# AC6901Demo1.net
KiCad netlist of a schematic drawn in Altium Designer
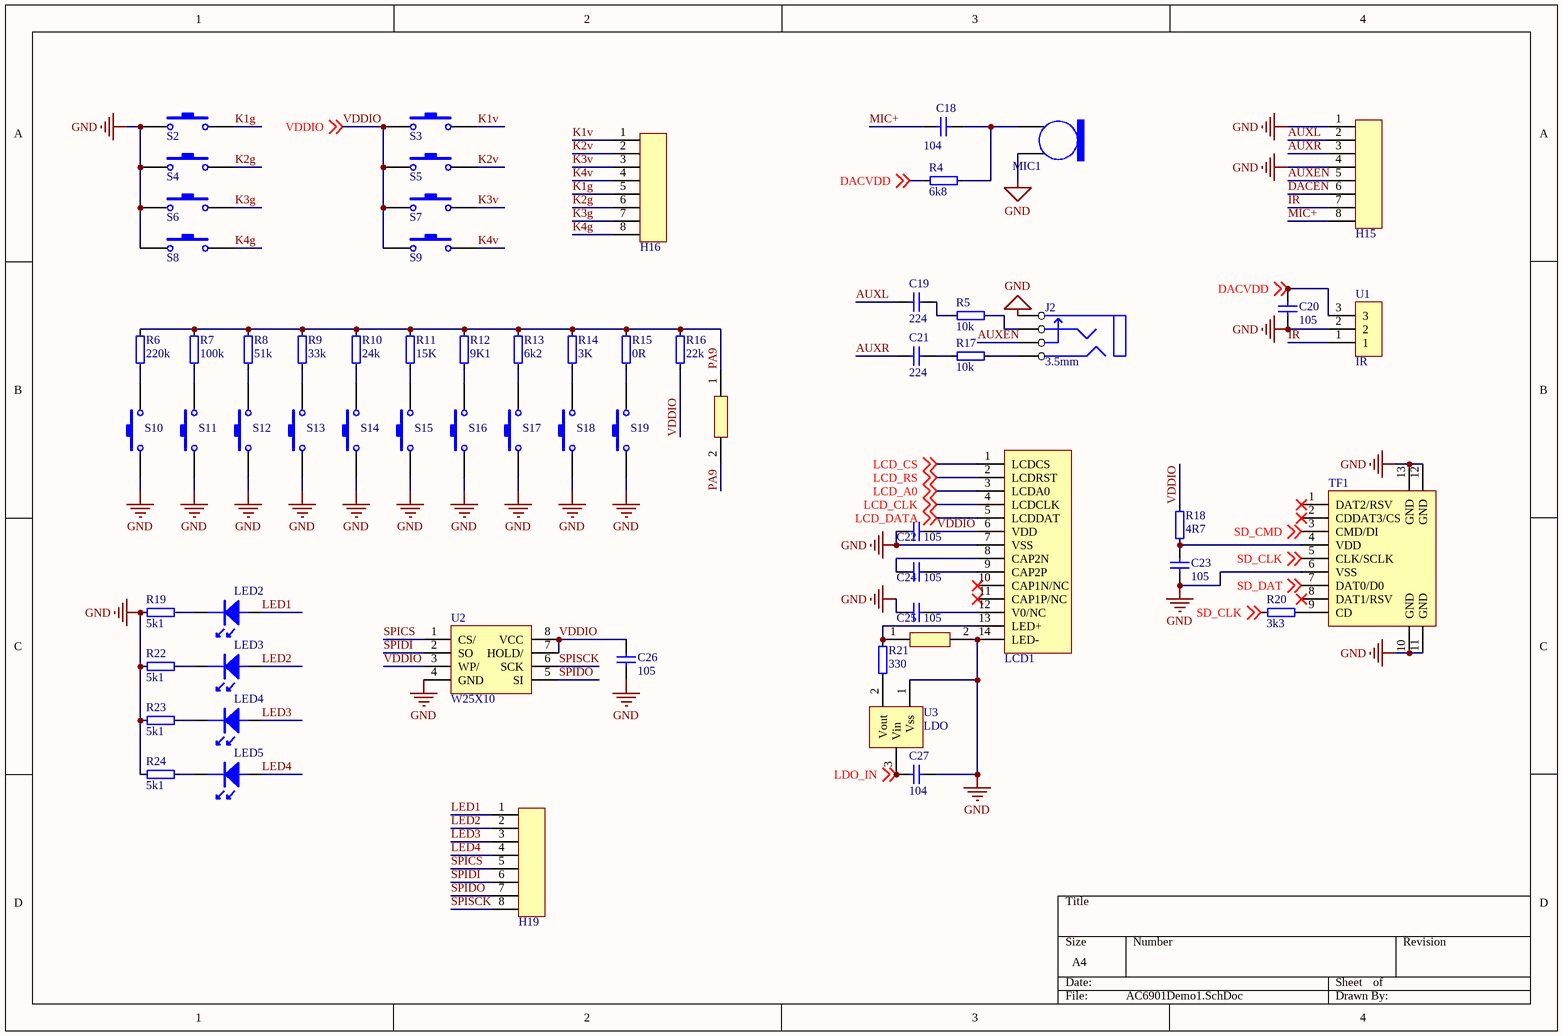
[diagram p0: AC6901Demo1.SchDoc]

(export (version "E")
  (design (tool "Eeschema 10.0.6"))
  (components
    (comp (ref "C18") (value "104") (footprint "Demo:C 0805") (libsource (lib "Demo") (part "CAP-MLCC")))
    (comp (ref "C19") (value "224") (footprint "Demo:C 0805") (libsource (lib "Demo") (part "CAP-MLCC")))
    (comp (ref "C20") (value "105") (footprint "Demo:C 0805") (libsource (lib "Demo") (part "CAP-MLCC")))
    (comp (ref "C21") (value "224") (footprint "Demo:C 0805") (libsource (lib "Demo") (part "CAP-MLCC")))
    (comp (ref "C22") (value "105") (footprint "Demo:C 0805") (libsource (lib "Demo") (part "CAP-MLCC")))
    (comp (ref "C23") (value "105") (footprint "Demo:C 0805") (libsource (lib "Demo") (part "CAP-MLCC")))
    (comp (ref "C24") (value "105") (footprint "Demo:C 0805") (libsource (lib "Demo") (part "CAP-MLCC")))
    (comp (ref "C25") (value "105") (footprint "Demo:C 0805") (libsource (lib "Demo") (part "CAP-MLCC")))
    (comp (ref "C26") (value "105") (footprint "Demo:C 0805") (libsource (lib "Demo") (part "CAP-MLCC")))
    (comp (ref "C27") (value "104") (footprint "Demo:C 0805") (libsource (lib "Demo") (part "CAP-MLCC")))
    (comp (ref "H15") (value "HDR1X8") (footprint "Demo:HDR1X8") (libsource (lib "Demo") (part "HDR1X8")))
    (comp (ref "H16") (value "HDR1X8") (footprint "Demo:HDR1X8") (libsource (lib "Demo") (part "HDR1X8")))
    (comp (ref "H17") (value "HDR2X1") (footprint "Demo:HDR2X1") (libsource (lib "") (part "HDR2X1_1")))
    (comp (ref "H18") (value "HDR2X1") (footprint "Demo:HDR2X1") (libsource (lib "Demo") (part "HDR2X1")))
    (comp (ref "H19") (value "HDR1X8") (footprint "Demo:HDR1X8") (libsource (lib "Demo") (part "HDR1X8")))
    (comp (ref "J2") (value "3.5mm") (footprint "Demo:AUX-3.5") (libsource (lib "Demo") (part "立体声插头")))
    (comp (ref "LCD1")
      (value "LCD12864_ST7567")
      (footprint "Demo:FPC-SMD_P0.80-14P")
      (libsource (lib "Demo") (part "LCD12864_ST7567"))
    )
    (comp (ref "LED2") (value "LED") (footprint "Demo:LED 0805B") (libsource (lib "Demo") (part "LED")))
    (comp (ref "LED3") (value "LED") (footprint "Demo:LED 0805B") (libsource (lib "Demo") (part "LED")))
    (comp (ref "LED4") (value "LED") (footprint "Demo:LED 0805B") (libsource (lib "Demo") (part "LED")))
    (comp (ref "LED5") (value "LED") (footprint "Demo:LED 0805B") (libsource (lib "Demo") (part "LED")))
    (comp (ref "MIC1") (value "MIC") (footprint "Demo:MIC") (libsource (lib "Demo") (part "MIC")))
    (comp (ref "R4") (value "6k8") (footprint "Demo:R 0805") (libsource (lib "Demo") (part "RES")))
    (comp (ref "R5") (value "10k") (footprint "Demo:R 0805") (libsource (lib "Demo") (part "RES")))
    (comp (ref "R6") (value "220k") (footprint "Demo:R 0805") (libsource (lib "Demo") (part "RES")))
    (comp (ref "R7") (value "100k") (footprint "Demo:R 0805") (libsource (lib "Demo") (part "RES")))
    (comp (ref "R8") (value "51k") (footprint "Demo:R 0805") (libsource (lib "Demo") (part "RES")))
    (comp (ref "R9") (value "33k") (footprint "Demo:R 0805") (libsource (lib "Demo") (part "RES")))
    (comp (ref "R10") (value "24k") (footprint "Demo:R 0805") (libsource (lib "Demo") (part "RES")))
    (comp (ref "R11") (value "15K") (footprint "Demo:R 0805") (libsource (lib "Demo") (part "RES")))
    (comp (ref "R12") (value "9K1") (footprint "Demo:R 0805") (libsource (lib "Demo") (part "RES")))
    (comp (ref "R13") (value "6k2") (footprint "Demo:R 0805") (libsource (lib "Demo") (part "RES")))
    (comp (ref "R14") (value "3K") (footprint "Demo:R 0805") (libsource (lib "Demo") (part "RES")))
    (comp (ref "R15") (value "0R") (footprint "Demo:R 0805") (libsource (lib "Demo") (part "RES")))
    (comp (ref "R16") (value "22k") (footprint "Demo:R 0805") (libsource (lib "Demo") (part "RES")))
    (comp (ref "R17") (value "10k") (footprint "Demo:R 0805") (libsource (lib "Demo") (part "RES")))
    (comp (ref "R18") (value "4R7") (footprint "Demo:R 0805") (libsource (lib "Demo") (part "RES")))
    (comp (ref "R19") (value "5k1") (footprint "Demo:R 0805") (libsource (lib "Demo") (part "RES")))
    (comp (ref "R20") (value "3k3") (footprint "Demo:R 0805") (libsource (lib "Demo") (part "RES")))
    (comp (ref "R21") (value "330") (footprint "Demo:R 0805") (libsource (lib "Demo") (part "RES")))
    (comp (ref "R22") (value "5k1") (footprint "Demo:R 0805") (libsource (lib "Demo") (part "RES")))
    (comp (ref "R23") (value "5k1") (footprint "Demo:R 0805") (libsource (lib "Demo") (part "RES")))
    (comp (ref "R24") (value "5k1") (footprint "Demo:R 0805") (libsource (lib "Demo") (part "RES")))
    (comp (ref "S2")
      (value "SW-PB")
      (footprint "Demo:TSW SMD-3*6*2.5")
      (fields (field (name "PUBLISHER") "Altium Limited"))
      (libsource (lib "Demo") (part "SW-PB"))
    )
    (comp (ref "S3")
      (value "SW-PB")
      (footprint "Demo:TSW SMD-3*6*2.5")
      (fields (field (name "PUBLISHER") "Altium Limited"))
      (libsource (lib "Demo") (part "SW-PB"))
    )
    (comp (ref "S4")
      (value "SW-PB")
      (footprint "Demo:TSW SMD-3*6*2.5")
      (fields (field (name "PUBLISHER") "Altium Limited"))
      (libsource (lib "Demo") (part "SW-PB"))
    )
    (comp (ref "S5")
      (value "SW-PB")
      (footprint "Demo:TSW SMD-3*6*2.5")
      (fields (field (name "PUBLISHER") "Altium Limited"))
      (libsource (lib "Demo") (part "SW-PB"))
    )
    (comp (ref "S6")
      (value "SW-PB")
      (footprint "Demo:TSW SMD-3*6*2.5")
      (fields (field (name "PUBLISHER") "Altium Limited"))
      (libsource (lib "Demo") (part "SW-PB"))
    )
    (comp (ref "S7")
      (value "SW-PB")
      (footprint "Demo:TSW SMD-3*6*2.5")
      (fields (field (name "PUBLISHER") "Altium Limited"))
      (libsource (lib "Demo") (part "SW-PB"))
    )
    (comp (ref "S8")
      (value "SW-PB")
      (footprint "Demo:TSW SMD-3*6*2.5")
      (fields (field (name "PUBLISHER") "Altium Limited"))
      (libsource (lib "Demo") (part "SW-PB"))
    )
    (comp (ref "S9")
      (value "SW-PB")
      (footprint "Demo:TSW SMD-3*6*2.5")
      (fields (field (name "PUBLISHER") "Altium Limited"))
      (libsource (lib "Demo") (part "SW-PB"))
    )
    (comp (ref "S10")
      (value "SW-PB")
      (footprint "Demo:TSW SMD-3*6*2.5")
      (fields (field (name "PUBLISHER") "Altium Limited"))
      (libsource (lib "Demo") (part "SW-PB"))
    )
    (comp (ref "S11")
      (value "SW-PB")
      (footprint "Demo:TSW SMD-3*6*2.5")
      (fields (field (name "PUBLISHER") "Altium Limited"))
      (libsource (lib "Demo") (part "SW-PB"))
    )
    (comp (ref "S12")
      (value "SW-PB")
      (footprint "Demo:TSW SMD-3*6*2.5")
      (fields (field (name "PUBLISHER") "Altium Limited"))
      (libsource (lib "Demo") (part "SW-PB"))
    )
    (comp (ref "S13")
      (value "SW-PB")
      (footprint "Demo:TSW SMD-3*6*2.5")
      (fields (field (name "PUBLISHER") "Altium Limited"))
      (libsource (lib "Demo") (part "SW-PB"))
    )
    (comp (ref "S14")
      (value "SW-PB")
      (footprint "Demo:TSW SMD-3*6*2.5")
      (fields (field (name "PUBLISHER") "Altium Limited"))
      (libsource (lib "Demo") (part "SW-PB"))
    )
    (comp (ref "S15")
      (value "SW-PB")
      (footprint "Demo:TSW SMD-3*6*2.5")
      (fields (field (name "PUBLISHER") "Altium Limited"))
      (libsource (lib "Demo") (part "SW-PB"))
    )
    (comp (ref "S16")
      (value "SW-PB")
      (footprint "Demo:TSW SMD-3*6*2.5")
      (fields (field (name "PUBLISHER") "Altium Limited"))
      (libsource (lib "Demo") (part "SW-PB"))
    )
    (comp (ref "S17")
      (value "SW-PB")
      (footprint "Demo:TSW SMD-3*6*2.5")
      (fields (field (name "PUBLISHER") "Altium Limited"))
      (libsource (lib "Demo") (part "SW-PB"))
    )
    (comp (ref "S18")
      (value "SW-PB")
      (footprint "Demo:TSW SMD-3*6*2.5")
      (fields (field (name "PUBLISHER") "Altium Limited"))
      (libsource (lib "Demo") (part "SW-PB"))
    )
    (comp (ref "S19")
      (value "SW-PB")
      (footprint "Demo:TSW SMD-3*6*2.5")
      (fields (field (name "PUBLISHER") "Altium Limited"))
      (libsource (lib "Demo") (part "SW-PB"))
    )
    (comp (ref "TF1") (value "TF") (footprint "Demo:TF") (libsource (lib "Demo") (part "TF")))
    (comp (ref "U1") (value "IR") (footprint "Demo:IR") (libsource (lib "Demo") (part "IR")))
    (comp (ref "U2") (value "W25X10") (footprint "Demo:SOIC8") (libsource (lib "Demo") (part "W25X10")))
    (comp (ref "U3") (value "LDO") (footprint "Demo:SOT23-3L") (libsource (lib "Demo") (part "LDO")))
  )
  (nets
    (net (code "1") (name "/AUXEN") (class "Default")
      (node (ref "H15") (pin "5") (pinfunction "5_5") (pintype "passive"))
      (node (ref "J2") (pin "4") (pinfunction "4_4") (pintype "passive"))
    )
    (net (code "2") (name "/AUXL") (class "Default")
      (node (ref "C19") (pin "1") (pinfunction "1_1") (pintype "passive"))
      (node (ref "H15") (pin "2") (pinfunction "2_2") (pintype "passive"))
    )
    (net (code "3") (name "/AUXR") (class "Default")
      (node (ref "C21") (pin "1") (pinfunction "1_1") (pintype "passive"))
      (node (ref "H15") (pin "3") (pinfunction "3_3") (pintype "passive"))
    )
    (net (code "4") (name "/DACEN") (class "Default")
      (node (ref "H15") (pin "6") (pinfunction "6_6") (pintype "passive"))
    )
    (net (code "5") (name "/IR") (class "Default")
      (node (ref "H15") (pin "7") (pinfunction "7_7") (pintype "passive"))
      (node (ref "U1") (pin "1") (pinfunction "1_1") (pintype "passive"))
    )
    (net (code "6") (name "/K1g") (class "Default")
      (node (ref "H16") (pin "5") (pinfunction "5_5") (pintype "passive"))
      (node (ref "S2") (pin "2") (pinfunction "2_2") (pintype "passive"))
    )
    (net (code "7") (name "/K1v") (class "Default")
      (node (ref "H16") (pin "1") (pinfunction "1_1") (pintype "passive"))
      (node (ref "S3") (pin "2") (pinfunction "2_2") (pintype "passive"))
    )
    (net (code "8") (name "/K2g") (class "Default")
      (node (ref "H16") (pin "6") (pinfunction "6_6") (pintype "passive"))
      (node (ref "S4") (pin "2") (pinfunction "2_2") (pintype "passive"))
    )
    (net (code "9") (name "/K2v") (class "Default")
      (node (ref "H16") (pin "2") (pinfunction "2_2") (pintype "passive"))
      (node (ref "S5") (pin "2") (pinfunction "2_2") (pintype "passive"))
    )
    (net (code "10") (name "/K3g") (class "Default")
      (node (ref "H16") (pin "7") (pinfunction "7_7") (pintype "passive"))
      (node (ref "S6") (pin "2") (pinfunction "2_2") (pintype "passive"))
    )
    (net (code "11") (name "/K3v") (class "Default")
      (node (ref "H16") (pin "3") (pinfunction "3_3") (pintype "passive"))
      (node (ref "S7") (pin "2") (pinfunction "2_2") (pintype "passive"))
    )
    (net (code "12") (name "/K4g") (class "Default")
      (node (ref "H16") (pin "8") (pinfunction "8_8") (pintype "passive"))
      (node (ref "S8") (pin "2") (pinfunction "2_2") (pintype "passive"))
    )
    (net (code "13") (name "/K4v") (class "Default")
      (node (ref "H16") (pin "4") (pinfunction "4_4") (pintype "passive"))
      (node (ref "S9") (pin "2") (pinfunction "2_2") (pintype "passive"))
    )
    (net (code "14") (name "/LED1") (class "Default")
      (node (ref "H19") (pin "1") (pinfunction "1_1") (pintype "passive"))
      (node (ref "LED2") (pin "1") (pinfunction "1_1") (pintype "passive"))
    )
    (net (code "15") (name "/LED2") (class "Default")
      (node (ref "H19") (pin "2") (pinfunction "2_2") (pintype "passive"))
      (node (ref "LED3") (pin "1") (pinfunction "1_1") (pintype "passive"))
    )
    (net (code "16") (name "/LED3") (class "Default")
      (node (ref "H19") (pin "3") (pinfunction "3_3") (pintype "passive"))
      (node (ref "LED4") (pin "1") (pinfunction "1_1") (pintype "passive"))
    )
    (net (code "17") (name "/LED4") (class "Default")
      (node (ref "H19") (pin "4") (pinfunction "4_4") (pintype "passive"))
      (node (ref "LED5") (pin "1") (pinfunction "1_1") (pintype "passive"))
    )
    (net (code "18") (name "/MIC+") (class "Default")
      (node (ref "C18") (pin "1") (pinfunction "1_1") (pintype "passive"))
      (node (ref "H15") (pin "8") (pinfunction "8_8") (pintype "passive"))
    )
    (net (code "19") (name "/PA9") (class "Default")
      (node (ref "H17") (pin "1") (pinfunction "1_1") (pintype "passive"))
      (node (ref "H17") (pin "2") (pinfunction "2_2") (pintype "passive"))
      (node (ref "R10") (pin "2") (pinfunction "2_2") (pintype "passive"))
      (node (ref "R11") (pin "2") (pinfunction "2_2") (pintype "passive"))
      (node (ref "R12") (pin "2") (pinfunction "2_2") (pintype "passive"))
      (node (ref "R13") (pin "2") (pinfunction "2_2") (pintype "passive"))
      (node (ref "R14") (pin "2") (pinfunction "2_2") (pintype "passive"))
      (node (ref "R15") (pin "2") (pinfunction "2_2") (pintype "passive"))
      (node (ref "R16") (pin "2") (pinfunction "2_2") (pintype "passive"))
      (node (ref "R6") (pin "2") (pinfunction "2_2") (pintype "passive"))
      (node (ref "R7") (pin "2") (pinfunction "2_2") (pintype "passive"))
      (node (ref "R8") (pin "2") (pinfunction "2_2") (pintype "passive"))
      (node (ref "R9") (pin "2") (pinfunction "2_2") (pintype "passive"))
    )
    (net (code "20") (name "/SPICS") (class "Default")
      (node (ref "H19") (pin "5") (pinfunction "5_5") (pintype "passive"))
      (node (ref "U2") (pin "1") (pinfunction "CS/_1") (pintype "passive"))
    )
    (net (code "21") (name "/SPIDI") (class "Default")
      (node (ref "H19") (pin "6") (pinfunction "6_6") (pintype "passive"))
      (node (ref "U2") (pin "2") (pinfunction "SO_2") (pintype "passive"))
    )
    (net (code "22") (name "/SPIDO") (class "Default")
      (node (ref "H19") (pin "7") (pinfunction "7_7") (pintype "passive"))
      (node (ref "U2") (pin "5") (pinfunction "SI_5") (pintype "passive"))
    )
    (net (code "23") (name "/SPISCK") (class "Default")
      (node (ref "H19") (pin "8") (pinfunction "8_8") (pintype "passive"))
      (node (ref "U2") (pin "6") (pinfunction "SCK_6") (pintype "passive"))
    )
    (net (code "24") (name "DACVDD") (class "Default")
      (node (ref "C20") (pin "2") (pinfunction "2_2") (pintype "passive"))
      (node (ref "R4") (pin "1") (pinfunction "1_1") (pintype "passive"))
      (node (ref "U1") (pin "3") (pinfunction "3_3") (pintype "passive"))
    )
    (net (code "25") (name "GND") (class "Default")
      (node (ref "C20") (pin "1") (pinfunction "1_1") (pintype "passive"))
      (node (ref "C22") (pin "1") (pinfunction "1_1") (pintype "passive"))
      (node (ref "C23") (pin "1") (pinfunction "1_1") (pintype "passive"))
      (node (ref "C25") (pin "1") (pinfunction "1_1") (pintype "passive"))
      (node (ref "C26") (pin "1") (pinfunction "1_1") (pintype "passive"))
      (node (ref "C27") (pin "1") (pinfunction "1_1") (pintype "passive"))
      (node (ref "H15") (pin "1") (pinfunction "1_1") (pintype "passive"))
      (node (ref "H15") (pin "4") (pinfunction "4_4") (pintype "passive"))
      (node (ref "H18") (pin "2") (pinfunction "2_2") (pintype "passive"))
      (node (ref "J2") (pin "1") (pinfunction "1_1") (pintype "passive"))
      (node (ref "LCD1") (pin "14") (pinfunction "LED-_14") (pintype "passive"))
      (node (ref "LCD1") (pin "7") (pinfunction "VSS_7") (pintype "passive"))
      (node (ref "MIC1") (pin "2") (pinfunction "2_2") (pintype "power_in"))
      (node (ref "R19") (pin "1") (pinfunction "1_1") (pintype "passive"))
      (node (ref "R22") (pin "1") (pinfunction "1_1") (pintype "passive"))
      (node (ref "R23") (pin "1") (pinfunction "1_1") (pintype "passive"))
      (node (ref "R24") (pin "1") (pinfunction "1_1") (pintype "passive"))
      (node (ref "S10") (pin "1") (pinfunction "1_1") (pintype "passive"))
      (node (ref "S11") (pin "1") (pinfunction "1_1") (pintype "passive"))
      (node (ref "S12") (pin "1") (pinfunction "1_1") (pintype "passive"))
      (node (ref "S13") (pin "1") (pinfunction "1_1") (pintype "passive"))
      (node (ref "S14") (pin "1") (pinfunction "1_1") (pintype "passive"))
      (node (ref "S15") (pin "1") (pinfunction "1_1") (pintype "passive"))
      (node (ref "S16") (pin "1") (pinfunction "1_1") (pintype "passive"))
      (node (ref "S17") (pin "1") (pinfunction "1_1") (pintype "passive"))
      (node (ref "S18") (pin "1") (pinfunction "1_1") (pintype "passive"))
      (node (ref "S19") (pin "1") (pinfunction "1_1") (pintype "passive"))
      (node (ref "S2") (pin "1") (pinfunction "1_1") (pintype "passive"))
      (node (ref "S4") (pin "1") (pinfunction "1_1") (pintype "passive"))
      (node (ref "S6") (pin "1") (pinfunction "1_1") (pintype "passive"))
      (node (ref "S8") (pin "1") (pinfunction "1_1") (pintype "passive"))
      (node (ref "TF1") (pin "10") (pinfunction "GND_10") (pintype "passive"))
      (node (ref "TF1") (pin "11") (pinfunction "GND_11") (pintype "passive"))
      (node (ref "TF1") (pin "12") (pinfunction "GND_12") (pintype "passive"))
      (node (ref "TF1") (pin "13") (pinfunction "GND_13") (pintype "passive"))
      (node (ref "TF1") (pin "6") (pinfunction "VSS_6") (pintype "passive"))
      (node (ref "U1") (pin "2") (pinfunction "2_2") (pintype "passive"))
      (node (ref "U2") (pin "4") (pinfunction "GND_4") (pintype "passive"))
      (node (ref "U3") (pin "1") (pinfunction "Vss_1") (pintype "passive"))
    )
    (net (code "26") (name "LCD_A0") (class "Default")
      (node (ref "LCD1") (pin "3") (pinfunction "LCDA0_3") (pintype "passive"))
    )
    (net (code "27") (name "LCD_CLK") (class "Default")
      (node (ref "LCD1") (pin "4") (pinfunction "LCDCLK_4") (pintype "passive"))
    )
    (net (code "28") (name "LCD_CS") (class "Default")
      (node (ref "LCD1") (pin "1") (pinfunction "LCDCS_1") (pintype "passive"))
    )
    (net (code "29") (name "LCD_DATA") (class "Default")
      (node (ref "LCD1") (pin "5") (pinfunction "LCDDAT_5") (pintype "passive"))
    )
    (net (code "30") (name "LCD_RS") (class "Default")
      (node (ref "LCD1") (pin "2") (pinfunction "LCDRST_2") (pintype "passive"))
    )
    (net (code "31") (name "LDO_IN") (class "Default")
      (node (ref "C27") (pin "2") (pinfunction "2_2") (pintype "passive"))
      (node (ref "U3") (pin "3") (pinfunction "Vin_3") (pintype "passive"))
    )
    (net (code "32") (name "Net-(C18-Pad2)") (class "Default")
      (node (ref "C18") (pin "2") (pinfunction "2_2") (pintype "passive"))
      (node (ref "MIC1") (pin "1") (pinfunction "1_1") (pintype "power_in"))
      (node (ref "R4") (pin "2") (pinfunction "2_2") (pintype "passive"))
    )
    (net (code "33") (name "Net-(C19-Pad2)") (class "Default")
      (node (ref "C19") (pin "2") (pinfunction "2_2") (pintype "passive"))
      (node (ref "R5") (pin "1") (pinfunction "1_1") (pintype "passive"))
    )
    (net (code "34") (name "Net-(C21-Pad2)") (class "Default")
      (node (ref "C21") (pin "2") (pinfunction "2_2") (pintype "passive"))
      (node (ref "R17") (pin "1") (pinfunction "1_1") (pintype "passive"))
    )
    (net (code "35") (name "Net-(J2-Pad2)") (class "Default")
      (node (ref "J2") (pin "2") (pinfunction "2_2") (pintype "passive"))
      (node (ref "R5") (pin "2") (pinfunction "2_2") (pintype "passive"))
    )
    (net (code "36") (name "Net-(J2-Pad3)") (class "Default")
      (node (ref "J2") (pin "3") (pinfunction "3_3") (pintype "passive"))
      (node (ref "R17") (pin "2") (pinfunction "2_2") (pintype "passive"))
    )
    (net (code "37") (name "Net-(LCD1-CAP2N)") (class "Default")
      (node (ref "C24") (pin "1") (pinfunction "1_1") (pintype "passive"))
      (node (ref "LCD1") (pin "8") (pinfunction "CAP2N_8") (pintype "passive"))
    )
    (net (code "38") (name "Net-(LCD1-CAP2P)") (class "Default")
      (node (ref "C24") (pin "2") (pinfunction "2_2") (pintype "passive"))
      (node (ref "LCD1") (pin "9") (pinfunction "CAP2P_9") (pintype "passive"))
    )
    (net (code "39") (name "Net-(LCD1-LED+)") (class "Default")
      (node (ref "H18") (pin "1") (pinfunction "1_1") (pintype "passive"))
      (node (ref "LCD1") (pin "13") (pinfunction "LED+_13") (pintype "passive"))
      (node (ref "R21") (pin "2") (pinfunction "2_2") (pintype "passive"))
    )
    (net (code "40") (name "Net-(LCD1-V0{slash}NC)") (class "Default")
      (node (ref "C25") (pin "2") (pinfunction "2_2") (pintype "passive"))
      (node (ref "LCD1") (pin "12") (pinfunction "V0/NC_12") (pintype "passive"))
    )
    (net (code "41") (name "Net-(LED2-Pad2)") (class "Default")
      (node (ref "LED2") (pin "2") (pinfunction "2_2") (pintype "passive"))
      (node (ref "R19") (pin "2") (pinfunction "2_2") (pintype "passive"))
    )
    (net (code "42") (name "Net-(LED3-Pad2)") (class "Default")
      (node (ref "LED3") (pin "2") (pinfunction "2_2") (pintype "passive"))
      (node (ref "R22") (pin "2") (pinfunction "2_2") (pintype "passive"))
    )
    (net (code "43") (name "Net-(LED4-Pad2)") (class "Default")
      (node (ref "LED4") (pin "2") (pinfunction "2_2") (pintype "passive"))
      (node (ref "R23") (pin "2") (pinfunction "2_2") (pintype "passive"))
    )
    (net (code "44") (name "Net-(LED5-Pad2)") (class "Default")
      (node (ref "LED5") (pin "2") (pinfunction "2_2") (pintype "passive"))
      (node (ref "R24") (pin "2") (pinfunction "2_2") (pintype "passive"))
    )
    (net (code "45") (name "Net-(R6-Pad1)") (class "Default")
      (node (ref "R6") (pin "1") (pinfunction "1_1") (pintype "passive"))
      (node (ref "S10") (pin "2") (pinfunction "2_2") (pintype "passive"))
    )
    (net (code "46") (name "Net-(R7-Pad1)") (class "Default")
      (node (ref "R7") (pin "1") (pinfunction "1_1") (pintype "passive"))
      (node (ref "S11") (pin "2") (pinfunction "2_2") (pintype "passive"))
    )
    (net (code "47") (name "Net-(R8-Pad1)") (class "Default")
      (node (ref "R8") (pin "1") (pinfunction "1_1") (pintype "passive"))
      (node (ref "S12") (pin "2") (pinfunction "2_2") (pintype "passive"))
    )
    (net (code "48") (name "Net-(R9-Pad1)") (class "Default")
      (node (ref "R9") (pin "1") (pinfunction "1_1") (pintype "passive"))
      (node (ref "S13") (pin "2") (pinfunction "2_2") (pintype "passive"))
    )
    (net (code "49") (name "Net-(R10-Pad1)") (class "Default")
      (node (ref "R10") (pin "1") (pinfunction "1_1") (pintype "passive"))
      (node (ref "S14") (pin "2") (pinfunction "2_2") (pintype "passive"))
    )
    (net (code "50") (name "Net-(R11-Pad1)") (class "Default")
      (node (ref "R11") (pin "1") (pinfunction "1_1") (pintype "passive"))
      (node (ref "S15") (pin "2") (pinfunction "2_2") (pintype "passive"))
    )
    (net (code "51") (name "Net-(R12-Pad1)") (class "Default")
      (node (ref "R12") (pin "1") (pinfunction "1_1") (pintype "passive"))
      (node (ref "S16") (pin "2") (pinfunction "2_2") (pintype "passive"))
    )
    (net (code "52") (name "Net-(R13-Pad1)") (class "Default")
      (node (ref "R13") (pin "1") (pinfunction "1_1") (pintype "passive"))
      (node (ref "S17") (pin "2") (pinfunction "2_2") (pintype "passive"))
    )
    (net (code "53") (name "Net-(R14-Pad1)") (class "Default")
      (node (ref "R14") (pin "1") (pinfunction "1_1") (pintype "passive"))
      (node (ref "S18") (pin "2") (pinfunction "2_2") (pintype "passive"))
    )
    (net (code "54") (name "Net-(R15-Pad1)") (class "Default")
      (node (ref "R15") (pin "1") (pinfunction "1_1") (pintype "passive"))
      (node (ref "S19") (pin "2") (pinfunction "2_2") (pintype "passive"))
    )
    (net (code "55") (name "Net-(TF1-CD)") (class "Default")
      (node (ref "R20") (pin "1") (pinfunction "1_1") (pintype "passive"))
      (node (ref "TF1") (pin "9") (pinfunction "CD_9") (pintype "passive"))
    )
    (net (code "56") (name "Net-(TF1-VDD)") (class "Default")
      (node (ref "C23") (pin "2") (pinfunction "2_2") (pintype "passive"))
      (node (ref "R18") (pin "1") (pinfunction "1_1") (pintype "passive"))
      (node (ref "TF1") (pin "4") (pinfunction "VDD_4") (pintype "passive"))
    )
    (net (code "57") (name "Net-(U3-Vout)") (class "Default")
      (node (ref "R21") (pin "1") (pinfunction "1_1") (pintype "passive"))
      (node (ref "U3") (pin "2") (pinfunction "Vout_2") (pintype "passive"))
    )
    (net (code "58") (name "SD_CLK") (class "Default")
      (node (ref "R20") (pin "2") (pinfunction "2_2") (pintype "passive"))
      (node (ref "TF1") (pin "5") (pinfunction "CLK/SCLK_5") (pintype "passive"))
    )
    (net (code "59") (name "SD_CMD") (class "Default")
      (node (ref "TF1") (pin "3") (pinfunction "CMD/DI_3") (pintype "passive"))
    )
    (net (code "60") (name "SD_DAT") (class "Default")
      (node (ref "TF1") (pin "7") (pinfunction "DAT0/D0_7") (pintype "passive"))
    )
    (net (code "61") (name "VDDIO") (class "Default")
      (node (ref "C22") (pin "2") (pinfunction "2_2") (pintype "passive"))
      (node (ref "C26") (pin "2") (pinfunction "2_2") (pintype "passive"))
      (node (ref "LCD1") (pin "6") (pinfunction "VDD_6") (pintype "passive"))
      (node (ref "R16") (pin "1") (pinfunction "1_1") (pintype "passive"))
      (node (ref "R18") (pin "2") (pinfunction "2_2") (pintype "passive"))
      (node (ref "S3") (pin "1") (pinfunction "1_1") (pintype "passive"))
      (node (ref "S5") (pin "1") (pinfunction "1_1") (pintype "passive"))
      (node (ref "S7") (pin "1") (pinfunction "1_1") (pintype "passive"))
      (node (ref "S9") (pin "1") (pinfunction "1_1") (pintype "passive"))
      (node (ref "U2") (pin "3") (pinfunction "WP/_3") (pintype "passive"))
      (node (ref "U2") (pin "7") (pinfunction "HOLD/_7") (pintype "passive"))
      (node (ref "U2") (pin "8") (pinfunction "VCC_8") (pintype "passive"))
    )
    (net (code "62") (name "unconnected-(LCD1-CAP1N{slash}NC-Pad10)") (class "Default")
      (node (ref "LCD1") (pin "10") (pinfunction "CAP1N/NC_10") (pintype "passive+no_connect"))
    )
    (net (code "63") (name "unconnected-(LCD1-CAP1P{slash}NC-Pad11)") (class "Default")
      (node (ref "LCD1") (pin "11") (pinfunction "CAP1P/NC_11") (pintype "passive+no_connect"))
    )
    (net (code "64") (name "unconnected-(TF1-CDDAT3{slash}CS-Pad2)") (class "Default")
      (node (ref "TF1") (pin "2") (pinfunction "CDDAT3/CS_2") (pintype "passive+no_connect"))
    )
    (net (code "65") (name "unconnected-(TF1-DAT1{slash}RSV-Pad8)") (class "Default")
      (node (ref "TF1") (pin "8") (pinfunction "DAT1/RSV_8") (pintype "passive+no_connect"))
    )
    (net (code "66") (name "unconnected-(TF1-DAT2{slash}RSV-Pad1)") (class "Default")
      (node (ref "TF1") (pin "1") (pinfunction "DAT2/RSV_1") (pintype "passive+no_connect"))
    )
  )
)
